# MIPI_CSI_0_and_1_Connectors.net
KiCad netlist of a schematic drawn in Altium Designer
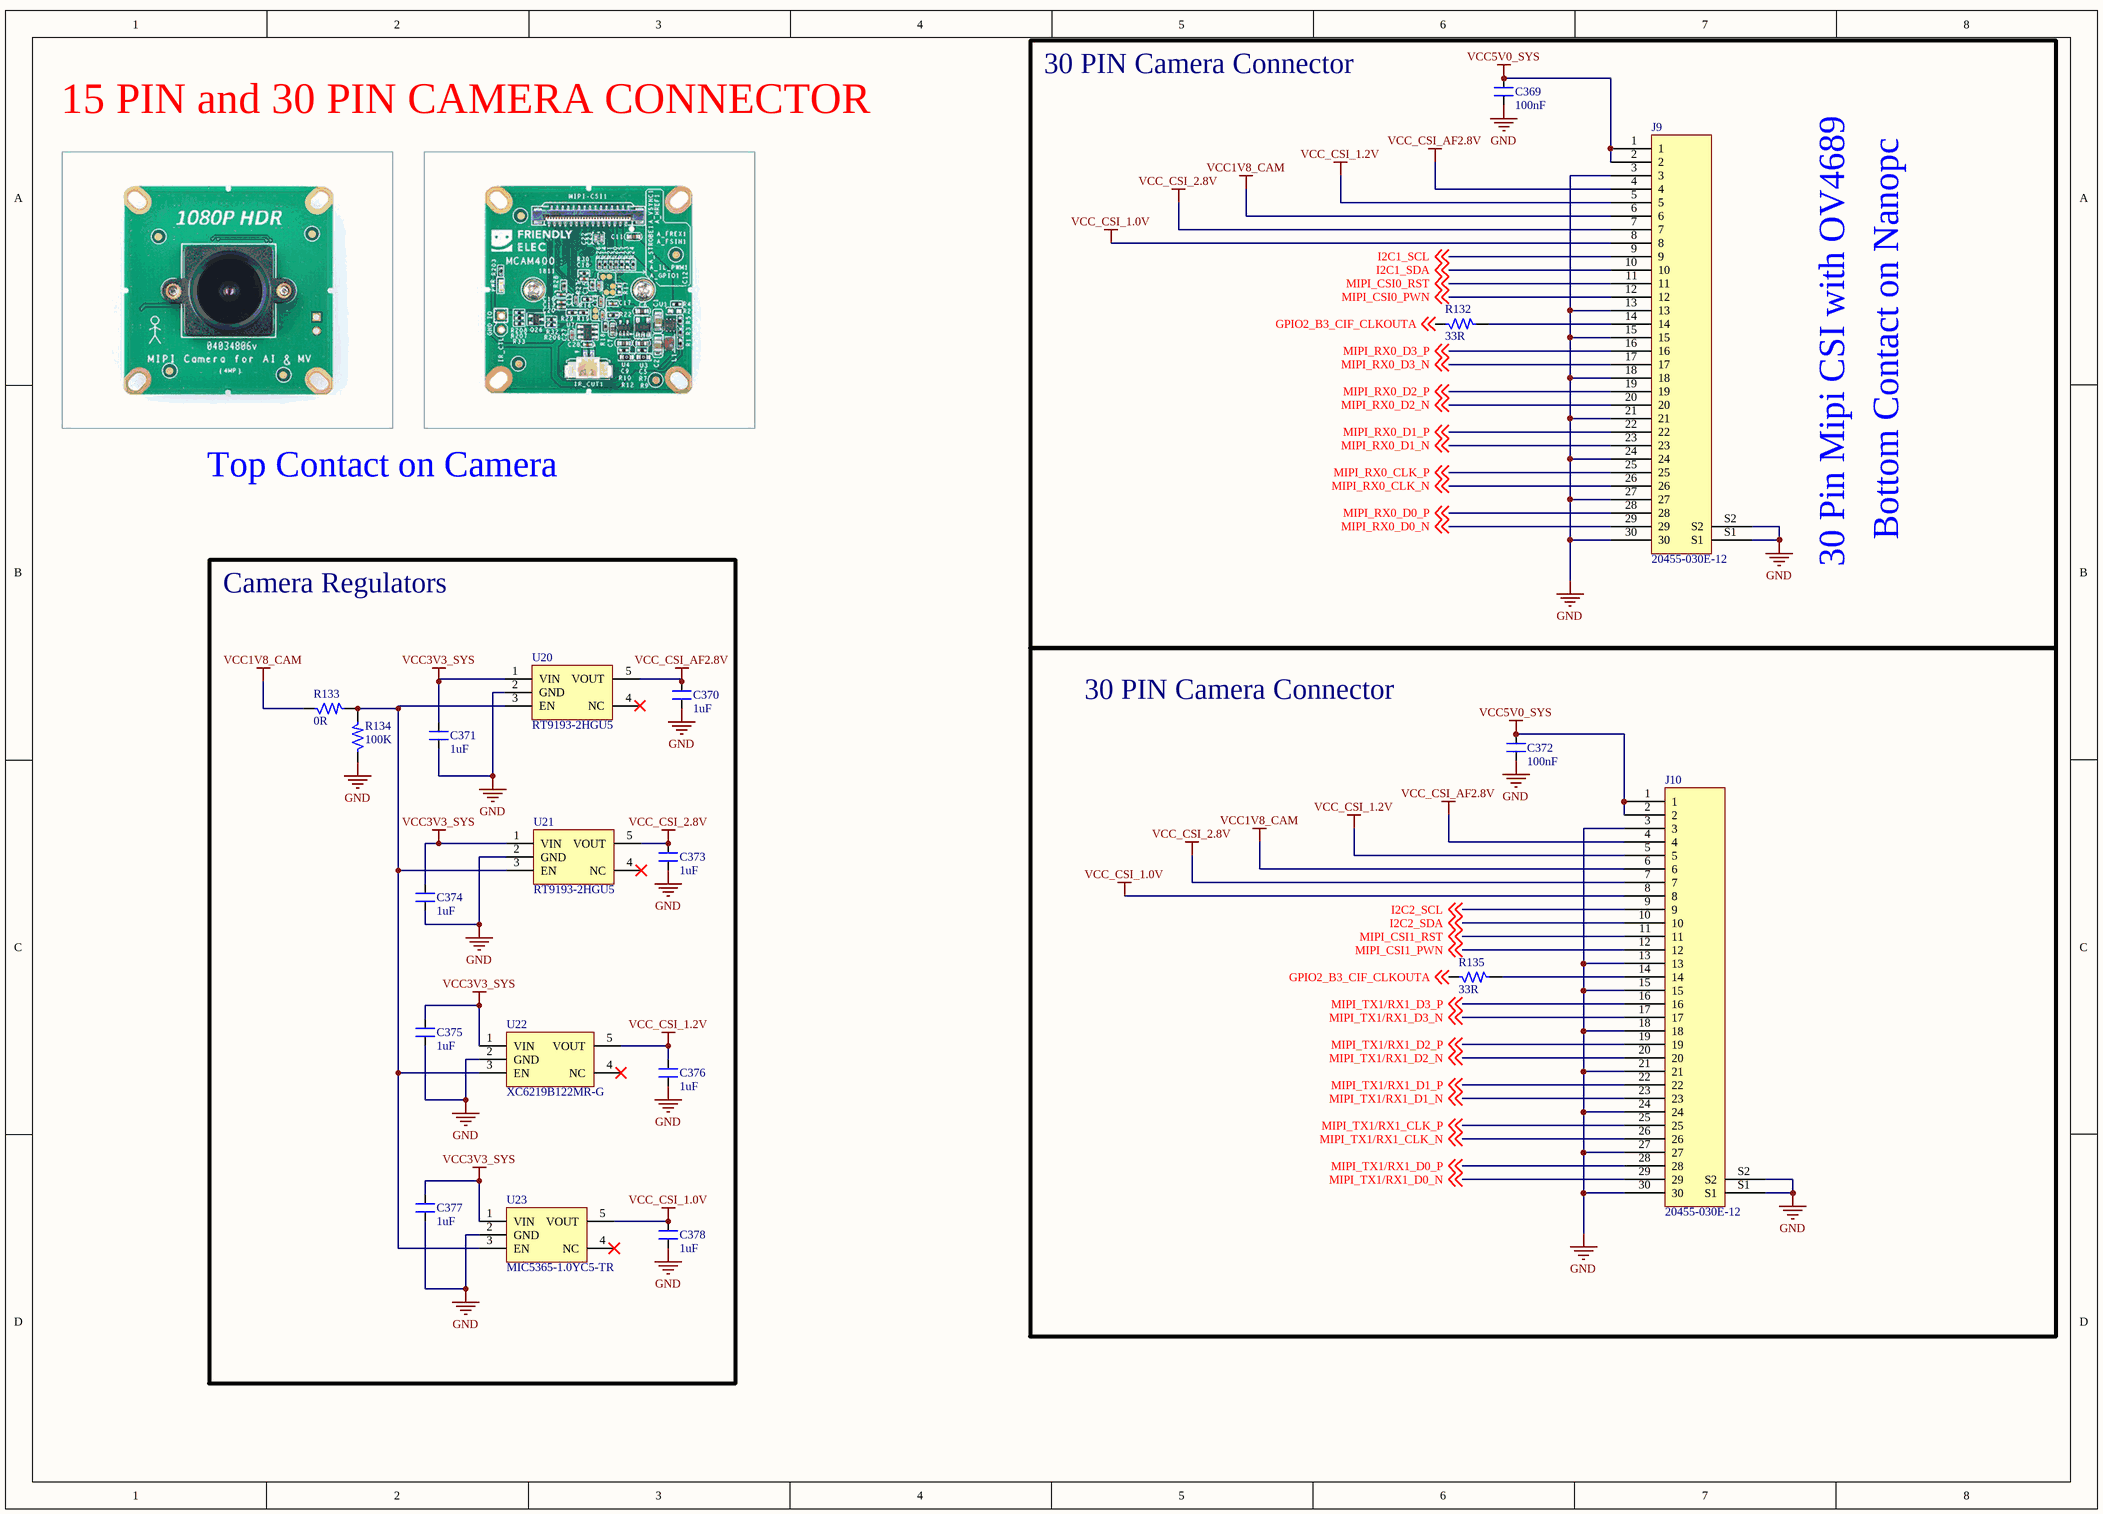
[diagram p0: MIPI CSI 0 and 1 Connectors.SchDoc]

(export (version "E")
  (design (tool "Eeschema 10.0.6"))
  (components
    (comp (ref "C369")
      (value "100nF")
      (footprint "CAP_0603")
      (description "0.1µF ±10% 10V Ceramic Capacitor X7R 0603 (1608 Metric)")
      (fields
        (field (name "MANUFACTURER") "Yageo")
        (field (name "MANUFACTURER PART NUMBER") "CC0603KRX7R6BB104")
      )
      (libsource (lib "RK3399 _Module_Schlib") (part "CAP_100nF-10V-5%-0603"))
    )
    (comp (ref "C370")
      (value "1uF")
      (footprint "CAP_0603")
      (description "1µF ±10% 10V Ceramic Capacitor X5R 0603 (1608 Metric)")
      (fields
        (field (name "MANUFACTURER") "Samsung Electro-Mechanics")
        (field (name "MANUFACTURER PART NUMBER") "CL10A105KP8NNNC")
      )
      (libsource (lib "RK3399 _Module_Schlib") (part "CAP_1uF-10V-5%-0603"))
    )
    (comp (ref "C371")
      (value "1uF")
      (footprint "CAP_0603")
      (description "1µF ±10% 10V Ceramic Capacitor X5R 0603 (1608 Metric)")
      (fields
        (field (name "MANUFACTURER") "Samsung Electro-Mechanics")
        (field (name "MANUFACTURER PART NUMBER") "CL10A105KP8NNNC")
      )
      (libsource (lib "RK3399 _Module_Schlib") (part "CAP_1uF-10V-5%-0603"))
    )
    (comp (ref "C372")
      (value "100nF")
      (footprint "CAP_0603")
      (description "0.1µF ±10% 10V Ceramic Capacitor X7R 0603 (1608 Metric)")
      (fields
        (field (name "MANUFACTURER") "Yageo")
        (field (name "MANUFACTURER PART NUMBER") "CC0603KRX7R6BB104")
      )
      (libsource (lib "RK3399 _Module_Schlib") (part "CAP_100nF-10V-5%-0603"))
    )
    (comp (ref "C373")
      (value "1uF")
      (footprint "CAP_0603")
      (description "1µF ±10% 10V Ceramic Capacitor X5R 0603 (1608 Metric)")
      (fields
        (field (name "MANUFACTURER") "Samsung Electro-Mechanics")
        (field (name "MANUFACTURER PART NUMBER") "CL10A105KP8NNNC")
      )
      (libsource (lib "RK3399 _Module_Schlib") (part "CAP_1uF-10V-5%-0603"))
    )
    (comp (ref "C374")
      (value "1uF")
      (footprint "CAP_0603")
      (description "1µF ±10% 10V Ceramic Capacitor X5R 0603 (1608 Metric)")
      (fields
        (field (name "MANUFACTURER") "Samsung Electro-Mechanics")
        (field (name "MANUFACTURER PART NUMBER") "CL10A105KP8NNNC")
      )
      (libsource (lib "RK3399 _Module_Schlib") (part "CAP_1uF-10V-5%-0603"))
    )
    (comp (ref "C375")
      (value "1uF")
      (footprint "CAP_0603")
      (description "1µF ±10% 10V Ceramic Capacitor X5R 0603 (1608 Metric)")
      (fields
        (field (name "MANUFACTURER") "Samsung Electro-Mechanics")
        (field (name "MANUFACTURER PART NUMBER") "CL10A105KP8NNNC")
      )
      (libsource (lib "RK3399 _Module_Schlib") (part "CAP_1uF-10V-5%-0603"))
    )
    (comp (ref "C376")
      (value "1uF")
      (footprint "CAP_0603")
      (description "1µF ±10% 10V Ceramic Capacitor X5R 0603 (1608 Metric)")
      (fields
        (field (name "MANUFACTURER") "Samsung Electro-Mechanics")
        (field (name "MANUFACTURER PART NUMBER") "CL10A105KP8NNNC")
      )
      (libsource (lib "RK3399 _Module_Schlib") (part "CAP_1uF-10V-5%-0603"))
    )
    (comp (ref "C377")
      (value "1uF")
      (footprint "CAP_0603")
      (description "1µF ±10% 10V Ceramic Capacitor X5R 0603 (1608 Metric)")
      (fields
        (field (name "MANUFACTURER") "Samsung Electro-Mechanics")
        (field (name "MANUFACTURER PART NUMBER") "CL10A105KP8NNNC")
      )
      (libsource (lib "RK3399 _Module_Schlib") (part "CAP_1uF-10V-5%-0603"))
    )
    (comp (ref "C378")
      (value "1uF")
      (footprint "CAP_0603")
      (description "1µF ±10% 10V Ceramic Capacitor X5R 0603 (1608 Metric)")
      (fields
        (field (name "MANUFACTURER") "Samsung Electro-Mechanics")
        (field (name "MANUFACTURER PART NUMBER") "CL10A105KP8NNNC")
      )
      (libsource (lib "RK3399 _Module_Schlib") (part "CAP_1uF-10V-5%-0603"))
    )
    (comp (ref "J9")
      (value "20455-030E-12")
      (footprint "CON30_19_68713014522 _SMD_RA")
      (description "FFC & FPC Connectors 0.5 FPC EASYON BTM CONT RA 30CKT ZIF")
      (fields (field (name "MANUFACTURER") "WE") (field (name "MANUFACTURER PART NUMBER") "68713014522"))
      (libsource (lib "RK3399 _Module_Schlib") (part "CON-PLG-FPC_30X1-19-RA-BC-SMD"))
    )
    (comp (ref "J10")
      (value "20455-030E-12")
      (footprint "CON30_19_68713014522 _SMD_RA")
      (description "FFC & FPC Connectors 0.5 FPC EASYON BTM CONT RA 30CKT ZIF")
      (fields (field (name "MANUFACTURER") "WE") (field (name "MANUFACTURER PART NUMBER") "68713014522"))
      (libsource (lib "RK3399 _Module_Schlib") (part "CON-PLG-FPC_30X1-19-RA-BC-SMD"))
    )
    (comp (ref "R132")
      (value "33R")
      (footprint "RES_0402")
      (description "33 Ohms ±1% 0.1W, 1/10W Chip Resistor 0402 (1005 Metric) Automotive AEC-Q200 Thick Film")
      (fields
        (field (name "MANUFACTURER") "Panasonic Electronic Components")
        (field (name "MANUFACTURER PART NUMBER") "ERJ-2RKF33R0X")
      )
      (libsource (lib "RK3399 _Module_Schlib") (part "RES_33R-0.1W-1%-0402"))
    )
    (comp (ref "R133")
      (value "0R")
      (footprint "RES_0603")
      (description "0 Ohms Jumper 0.1W, 1/10W Chip Resistor 0603 (1608 Metric) Thick Film")
      (fields
        (field (name "MANUFACTURER") "Yageo")
        (field (name "MANUFACTURER PART NUMBER") "RC0603JR-070RL")
      )
      (libsource (lib "RK3399 _Module_Schlib") (part "RES_0R-0.1W-1%-0603"))
    )
    (comp (ref "R134")
      (value "100K")
      (footprint "RES_0603")
      (description "100 kOhms ±1% 0.1W, 1/10W Chip Resistor 0603 (1608 Metric) Automotive AEC-Q200 Thick Film")
      (fields
        (field (name "MANUFACTURER") "tackpole Electronics Inc")
        (field (name "MANUFACTURER PART NUMBER") "RMCF0603FT100K")
      )
      (libsource (lib "RK3399 _Module_Schlib") (part "RES_100K-0.1W-1%-0603"))
    )
    (comp (ref "R135")
      (value "33R")
      (footprint "RES_0402")
      (description "33 Ohms ±1% 0.1W, 1/10W Chip Resistor 0402 (1005 Metric) Automotive AEC-Q200 Thick Film")
      (fields
        (field (name "MANUFACTURER") "Panasonic Electronic Components")
        (field (name "MANUFACTURER PART NUMBER") "ERJ-2RKF33R0X")
      )
      (libsource (lib "RK3399 _Module_Schlib") (part "RES_33R-0.1W-1%-0402"))
    )
    (comp (ref "U20")
      (value "RT9193-2HGU5")
      (footprint "SOT23-5")
      (description "Fixed LDO Voltage Regulator, 2.5V to 5.5V, 220mV Dropout, 2.85Vout, 300mAout, SC-70-5")
      (fields (field (name "MANUFACTURER") "RICHTEK"))
      (libsource (lib "RK3399 _Module_Schlib") (part "REG_2.5V-5.5V-0.3A-SC-70-5"))
    )
    (comp (ref "U21")
      (value "RT9193-2HGU5")
      (footprint "SOT23-5")
      (description "Fixed LDO Voltage Regulator, 2.5V to 5.5V, 220mV Dropout, 2.85Vout, 300mAout, SC-70-5")
      (fields (field (name "MANUFACTURER") "RICHTEK"))
      (libsource (lib "RK3399 _Module_Schlib") (part "REG_2.5V-5.5V-0.3A-SC-70-5"))
    )
    (comp (ref "U22")
      (value "XC6219B122MR-G")
      (footprint "SOT23-5")
      (description "LDO Voltage Regulators")
      (fields (field (name "MANUFACTURER") "Torex Semiconductor"))
      (libsource (lib "RK3399 _Module_Schlib") (part "REG_1.2V-6V-0.15A-SOT-25-5"))
    )
    (comp (ref "U23")
      (value "MIC5365-1.0YC5-TR")
      (footprint "SOT23-5")
      (description "LDO Voltage Regulators Ultra Small Single 150mA LDO")
      (fields (field (name "MANUFACTURER") "Microchip Technology / Micrel"))
      (libsource (lib "RK3399 _Module_Schlib") (part "REG_1V-5.5V-0.15A-SC-70-5"))
    )
  )
  (nets
    (net (code "1") (name "GND") (class "Default")
      (node (ref "C369") (pin "1") (pinfunction "1_1") (pintype "passive"))
      (node (ref "C370") (pin "1") (pinfunction "1_1") (pintype "passive"))
      (node (ref "C371") (pin "1") (pinfunction "1_1") (pintype "passive"))
      (node (ref "C372") (pin "1") (pinfunction "1_1") (pintype "passive"))
      (node (ref "C373") (pin "1") (pinfunction "1_1") (pintype "passive"))
      (node (ref "C374") (pin "1") (pinfunction "1_1") (pintype "passive"))
      (node (ref "C375") (pin "1") (pinfunction "1_1") (pintype "passive"))
      (node (ref "C376") (pin "1") (pinfunction "1_1") (pintype "passive"))
      (node (ref "C377") (pin "1") (pinfunction "1_1") (pintype "passive"))
      (node (ref "C378") (pin "1") (pinfunction "1_1") (pintype "passive"))
      (node (ref "J10") (pin "13") (pinfunction "13_13") (pintype "passive"))
      (node (ref "J10") (pin "15") (pinfunction "15_15") (pintype "passive"))
      (node (ref "J10") (pin "18") (pinfunction "18_18") (pintype "passive"))
      (node (ref "J10") (pin "21") (pinfunction "21_21") (pintype "passive"))
      (node (ref "J10") (pin "24") (pinfunction "24_24") (pintype "passive"))
      (node (ref "J10") (pin "27") (pinfunction "27_27") (pintype "passive"))
      (node (ref "J10") (pin "3") (pinfunction "3_3") (pintype "passive"))
      (node (ref "J10") (pin "30") (pinfunction "30_30") (pintype "passive"))
      (node (ref "J10") (pin "S1") (pinfunction "S1_S1") (pintype "passive"))
      (node (ref "J10") (pin "S2") (pinfunction "S2_S2") (pintype "passive"))
      (node (ref "J9") (pin "13") (pinfunction "13_13") (pintype "passive"))
      (node (ref "J9") (pin "15") (pinfunction "15_15") (pintype "passive"))
      (node (ref "J9") (pin "18") (pinfunction "18_18") (pintype "passive"))
      (node (ref "J9") (pin "21") (pinfunction "21_21") (pintype "passive"))
      (node (ref "J9") (pin "24") (pinfunction "24_24") (pintype "passive"))
      (node (ref "J9") (pin "27") (pinfunction "27_27") (pintype "passive"))
      (node (ref "J9") (pin "3") (pinfunction "3_3") (pintype "passive"))
      (node (ref "J9") (pin "30") (pinfunction "30_30") (pintype "passive"))
      (node (ref "J9") (pin "S1") (pinfunction "S1_S1") (pintype "passive"))
      (node (ref "J9") (pin "S2") (pinfunction "S2_S2") (pintype "passive"))
      (node (ref "R134") (pin "1") (pinfunction "1_1") (pintype "passive"))
      (node (ref "U20") (pin "2") (pinfunction "GND_2") (pintype "passive"))
      (node (ref "U21") (pin "2") (pinfunction "GND_2") (pintype "passive"))
      (node (ref "U22") (pin "2") (pinfunction "GND_2") (pintype "passive"))
      (node (ref "U23") (pin "2") (pinfunction "GND_2") (pintype "passive"))
    )
    (net (code "2") (name "GPIO2_B3_CIF_CLKOUTA") (class "Default")
      (node (ref "R132") (pin "1") (pinfunction "1_1") (pintype "passive"))
      (node (ref "R135") (pin "1") (pinfunction "1_1") (pintype "passive"))
    )
    (net (code "3") (name "I2C1_SCL") (class "Default")
      (node (ref "J9") (pin "9") (pinfunction "9_9") (pintype "passive"))
    )
    (net (code "4") (name "I2C1_SDA") (class "Default")
      (node (ref "J9") (pin "10") (pinfunction "10_10") (pintype "passive"))
    )
    (net (code "5") (name "I2C2_SCL") (class "Default")
      (node (ref "J10") (pin "9") (pinfunction "9_9") (pintype "passive"))
    )
    (net (code "6") (name "I2C2_SDA") (class "Default")
      (node (ref "J10") (pin "10") (pinfunction "10_10") (pintype "passive"))
    )
    (net (code "7") (name "MIPI_CSI0_PWN") (class "Default")
      (node (ref "J9") (pin "12") (pinfunction "12_12") (pintype "passive"))
    )
    (net (code "8") (name "MIPI_CSI0_RST") (class "Default")
      (node (ref "J9") (pin "11") (pinfunction "11_11") (pintype "passive"))
    )
    (net (code "9") (name "MIPI_CSI1_PWN") (class "Default")
      (node (ref "J10") (pin "12") (pinfunction "12_12") (pintype "passive"))
    )
    (net (code "10") (name "MIPI_CSI1_RST") (class "Default")
      (node (ref "J10") (pin "11") (pinfunction "11_11") (pintype "passive"))
    )
    (net (code "11") (name "MIPI_RX0_CLK_N") (class "Default")
      (node (ref "J9") (pin "26") (pinfunction "26_26") (pintype "passive"))
    )
    (net (code "12") (name "MIPI_RX0_CLK_P") (class "Default")
      (node (ref "J9") (pin "25") (pinfunction "25_25") (pintype "passive"))
    )
    (net (code "13") (name "MIPI_RX0_D0_N") (class "Default")
      (node (ref "J9") (pin "29") (pinfunction "29_29") (pintype "passive"))
    )
    (net (code "14") (name "MIPI_RX0_D0_P") (class "Default")
      (node (ref "J9") (pin "28") (pinfunction "28_28") (pintype "passive"))
    )
    (net (code "15") (name "MIPI_RX0_D1_N") (class "Default")
      (node (ref "J9") (pin "23") (pinfunction "23_23") (pintype "passive"))
    )
    (net (code "16") (name "MIPI_RX0_D1_P") (class "Default")
      (node (ref "J9") (pin "22") (pinfunction "22_22") (pintype "passive"))
    )
    (net (code "17") (name "MIPI_RX0_D2_N") (class "Default")
      (node (ref "J9") (pin "20") (pinfunction "20_20") (pintype "passive"))
    )
    (net (code "18") (name "MIPI_RX0_D2_P") (class "Default")
      (node (ref "J9") (pin "19") (pinfunction "19_19") (pintype "passive"))
    )
    (net (code "19") (name "MIPI_RX0_D3_N") (class "Default")
      (node (ref "J9") (pin "17") (pinfunction "17_17") (pintype "passive"))
    )
    (net (code "20") (name "MIPI_RX0_D3_P") (class "Default")
      (node (ref "J9") (pin "16") (pinfunction "16_16") (pintype "passive"))
    )
    (net (code "21") (name "MIPI_TX1{slash}RX1_CLK_N") (class "Default")
      (node (ref "J10") (pin "26") (pinfunction "26_26") (pintype "passive"))
    )
    (net (code "22") (name "MIPI_TX1{slash}RX1_CLK_P") (class "Default")
      (node (ref "J10") (pin "25") (pinfunction "25_25") (pintype "passive"))
    )
    (net (code "23") (name "MIPI_TX1{slash}RX1_D0_N") (class "Default")
      (node (ref "J10") (pin "29") (pinfunction "29_29") (pintype "passive"))
    )
    (net (code "24") (name "MIPI_TX1{slash}RX1_D0_P") (class "Default")
      (node (ref "J10") (pin "28") (pinfunction "28_28") (pintype "passive"))
    )
    (net (code "25") (name "MIPI_TX1{slash}RX1_D1_N") (class "Default")
      (node (ref "J10") (pin "23") (pinfunction "23_23") (pintype "passive"))
    )
    (net (code "26") (name "MIPI_TX1{slash}RX1_D1_P") (class "Default")
      (node (ref "J10") (pin "22") (pinfunction "22_22") (pintype "passive"))
    )
    (net (code "27") (name "MIPI_TX1{slash}RX1_D2_N") (class "Default")
      (node (ref "J10") (pin "20") (pinfunction "20_20") (pintype "passive"))
    )
    (net (code "28") (name "MIPI_TX1{slash}RX1_D2_P") (class "Default")
      (node (ref "J10") (pin "19") (pinfunction "19_19") (pintype "passive"))
    )
    (net (code "29") (name "MIPI_TX1{slash}RX1_D3_N") (class "Default")
      (node (ref "J10") (pin "17") (pinfunction "17_17") (pintype "passive"))
    )
    (net (code "30") (name "MIPI_TX1{slash}RX1_D3_P") (class "Default")
      (node (ref "J10") (pin "16") (pinfunction "16_16") (pintype "passive"))
    )
    (net (code "31") (name "Net-(J9-Pad14)") (class "Default")
      (node (ref "J9") (pin "14") (pinfunction "14_14") (pintype "passive"))
      (node (ref "R132") (pin "2") (pinfunction "2_2") (pintype "passive"))
    )
    (net (code "32") (name "Net-(J10-Pad14)") (class "Default")
      (node (ref "J10") (pin "14") (pinfunction "14_14") (pintype "passive"))
      (node (ref "R135") (pin "2") (pinfunction "2_2") (pintype "passive"))
    )
    (net (code "33") (name "Net-(U20-EN)") (class "Default")
      (node (ref "R133") (pin "2") (pinfunction "2_2") (pintype "passive"))
      (node (ref "R134") (pin "2") (pinfunction "2_2") (pintype "passive"))
      (node (ref "U20") (pin "3") (pinfunction "EN_3") (pintype "passive"))
      (node (ref "U21") (pin "3") (pinfunction "EN_3") (pintype "passive"))
      (node (ref "U22") (pin "3") (pinfunction "EN_3") (pintype "passive"))
      (node (ref "U23") (pin "3") (pinfunction "EN_3") (pintype "passive"))
    )
    (net (code "34") (name "VCC1V8_CAM") (class "Default")
      (node (ref "J10") (pin "6") (pinfunction "6_6") (pintype "passive"))
      (node (ref "J9") (pin "6") (pinfunction "6_6") (pintype "passive"))
      (node (ref "R133") (pin "1") (pinfunction "1_1") (pintype "passive"))
    )
    (net (code "35") (name "VCC3V3_SYS") (class "Default")
      (node (ref "C371") (pin "2") (pinfunction "2_2") (pintype "passive"))
      (node (ref "C374") (pin "2") (pinfunction "2_2") (pintype "passive"))
      (node (ref "C375") (pin "2") (pinfunction "2_2") (pintype "passive"))
      (node (ref "C377") (pin "2") (pinfunction "2_2") (pintype "passive"))
      (node (ref "U20") (pin "1") (pinfunction "VIN_1") (pintype "passive"))
      (node (ref "U21") (pin "1") (pinfunction "VIN_1") (pintype "passive"))
      (node (ref "U22") (pin "1") (pinfunction "VIN_1") (pintype "passive"))
      (node (ref "U23") (pin "1") (pinfunction "VIN_1") (pintype "passive"))
    )
    (net (code "36") (name "VCC5V0_SYS") (class "Default")
      (node (ref "C369") (pin "2") (pinfunction "2_2") (pintype "passive"))
      (node (ref "C372") (pin "2") (pinfunction "2_2") (pintype "passive"))
      (node (ref "J10") (pin "1") (pinfunction "1_1") (pintype "passive"))
      (node (ref "J10") (pin "2") (pinfunction "2_2") (pintype "passive"))
      (node (ref "J9") (pin "1") (pinfunction "1_1") (pintype "passive"))
      (node (ref "J9") (pin "2") (pinfunction "2_2") (pintype "passive"))
    )
    (net (code "37") (name "VCC_CSI_1.0V") (class "Default")
      (node (ref "C378") (pin "2") (pinfunction "2_2") (pintype "passive"))
      (node (ref "J10") (pin "8") (pinfunction "8_8") (pintype "passive"))
      (node (ref "J9") (pin "8") (pinfunction "8_8") (pintype "passive"))
      (node (ref "U23") (pin "5") (pinfunction "VOUT_5") (pintype "passive"))
    )
    (net (code "38") (name "VCC_CSI_1.2V") (class "Default")
      (node (ref "C376") (pin "2") (pinfunction "2_2") (pintype "passive"))
      (node (ref "J10") (pin "5") (pinfunction "5_5") (pintype "passive"))
      (node (ref "J9") (pin "5") (pinfunction "5_5") (pintype "passive"))
      (node (ref "U22") (pin "5") (pinfunction "VOUT_5") (pintype "passive"))
    )
    (net (code "39") (name "VCC_CSI_2.8V") (class "Default")
      (node (ref "C373") (pin "2") (pinfunction "2_2") (pintype "passive"))
      (node (ref "J10") (pin "7") (pinfunction "7_7") (pintype "passive"))
      (node (ref "J9") (pin "7") (pinfunction "7_7") (pintype "passive"))
      (node (ref "U21") (pin "5") (pinfunction "VOUT_5") (pintype "passive"))
    )
    (net (code "40") (name "VCC_CSI_AF2.8V") (class "Default")
      (node (ref "C370") (pin "2") (pinfunction "2_2") (pintype "passive"))
      (node (ref "J10") (pin "4") (pinfunction "4_4") (pintype "passive"))
      (node (ref "J9") (pin "4") (pinfunction "4_4") (pintype "passive"))
      (node (ref "U20") (pin "5") (pinfunction "VOUT_5") (pintype "passive"))
    )
    (net (code "41") (name "unconnected-(U20-NC-Pad4)") (class "Default")
      (node (ref "U20") (pin "4") (pinfunction "NC_4") (pintype "passive+no_connect"))
    )
    (net (code "42") (name "unconnected-(U21-NC-Pad4)") (class "Default")
      (node (ref "U21") (pin "4") (pinfunction "NC_4") (pintype "passive+no_connect"))
    )
    (net (code "43") (name "unconnected-(U22-NC-Pad4)") (class "Default")
      (node (ref "U22") (pin "4") (pinfunction "NC_4") (pintype "passive+no_connect"))
    )
    (net (code "44") (name "unconnected-(U23-NC-Pad4)") (class "Default")
      (node (ref "U23") (pin "4") (pinfunction "NC_4") (pintype "passive+no_connect"))
    )
  )
)
